# 3-Pumps-Driver.net
KiCad netlist of a schematic drawn in EAGLE
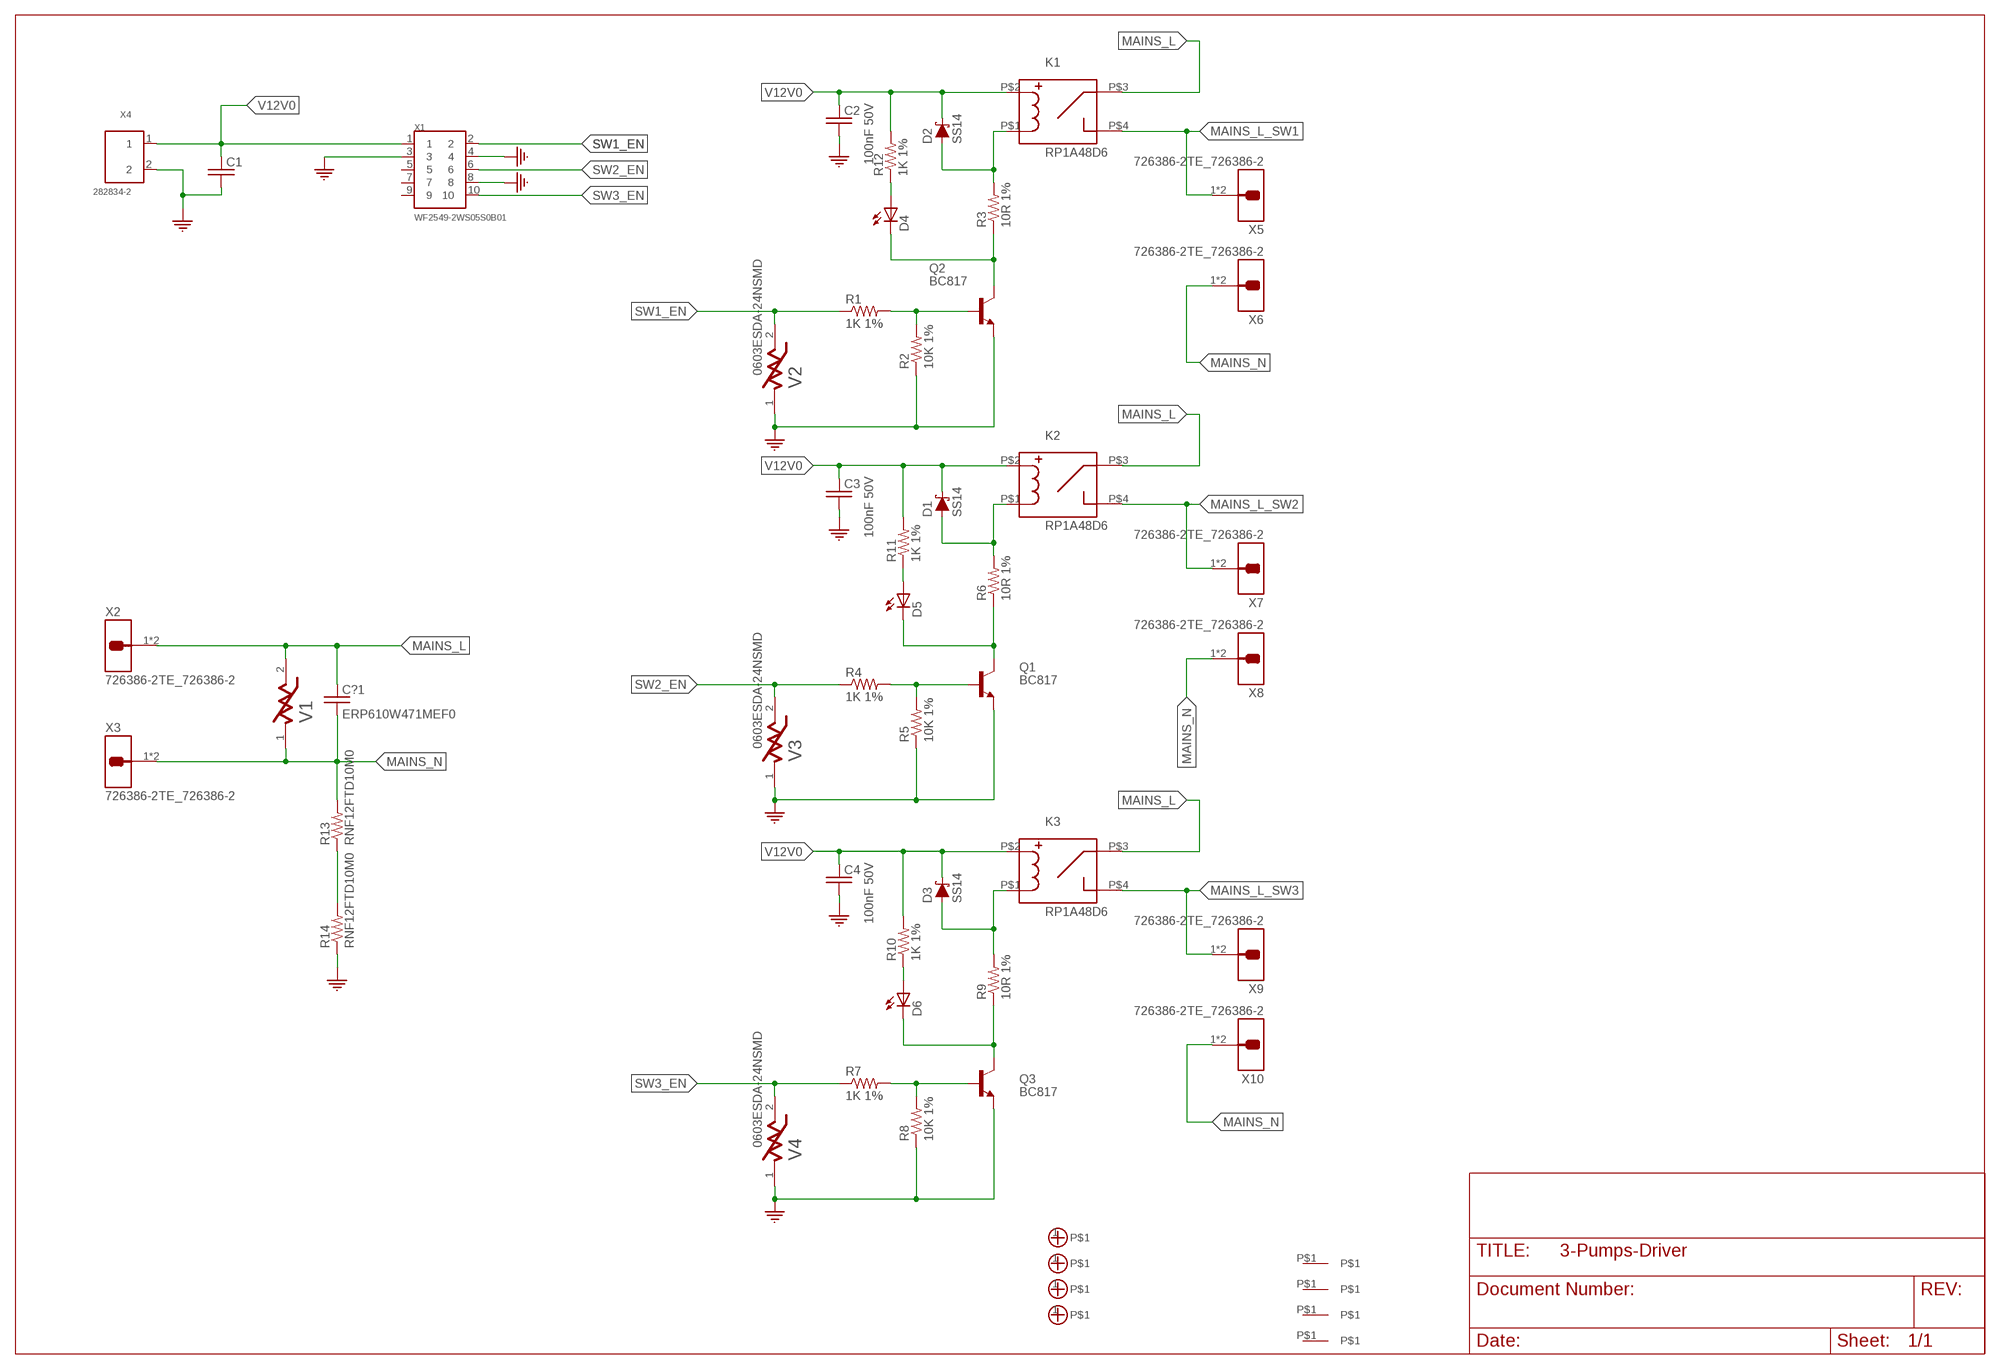
[diagram p0: schematic, sheet 1]

(export (version "E")
  (design (tool "Eeschema 10.0.6"))
  (components
    (comp (ref "C1")
      (value "C_0603EIA0603")
      (footprint "eagle-import:EIA0603")
      (libsource (lib "eagle-import") (part "C_0603EIA0603"))
    )
    (comp (ref "C2")
      (value "100nF 50V")
      (footprint "eagle-import:EIA0603")
      (libsource (lib "eagle-import") (part "C_0603EIA0603"))
    )
    (comp (ref "C3")
      (value "100nF 50V")
      (footprint "eagle-import:EIA0603")
      (libsource (lib "eagle-import") (part "C_0603EIA0603"))
    )
    (comp (ref "C4")
      (value "100nF 50V")
      (footprint "eagle-import:EIA0603")
      (libsource (lib "eagle-import") (part "C_0603EIA0603"))
    )
    (comp (ref "C?1")
      (value "ERP610W471MEF0")
      (footprint "eagle-import:CAPACITOR-FILM-RM12.5MM-12MM")
      (fields (field (name "MFR") "Vishay"))
      (libsource (lib "eagle-import") (part "ERP610W471MEF0"))
    )
    (comp (ref "D1")
      (value "SS14")
      (footprint "eagle-import:SMA")
      (fields (field (name "MFR") "MCC"))
      (libsource (lib "eagle-import") (part "SS14"))
    )
    (comp (ref "D2")
      (value "SS14")
      (footprint "eagle-import:SMA")
      (fields (field (name "MFR") "MCC"))
      (libsource (lib "eagle-import") (part "SS14"))
    )
    (comp (ref "D3")
      (value "SS14")
      (footprint "eagle-import:SMA")
      (fields (field (name "MFR") "MCC"))
      (libsource (lib "eagle-import") (part "SS14"))
    )
    (comp (ref "D4")
      (value "26-21/GPC-F3138B/CA")
      (footprint "eagle-import:SMD1206-LED")
      (fields (field (name "MFR") "Everlight"))
      (libsource (lib "eagle-import") (part "26-21/GPC-F3138B/CA"))
    )
    (comp (ref "D5")
      (value "26-21/GPC-F3138B/CA")
      (footprint "eagle-import:SMD1206-LED")
      (fields (field (name "MFR") "Everlight"))
      (libsource (lib "eagle-import") (part "26-21/GPC-F3138B/CA"))
    )
    (comp (ref "D6")
      (value "26-21/GPC-F3138B/CA")
      (footprint "eagle-import:SMD1206-LED")
      (fields (field (name "MFR") "Everlight"))
      (libsource (lib "eagle-import") (part "26-21/GPC-F3138B/CA"))
    )
    (comp (ref "FID1")
      (value "FIDUCIAL")
      (footprint "eagle-import:FIDUCIAL")
      (libsource (lib "eagle-import") (part "FIDUCIAL"))
    )
    (comp (ref "FID2")
      (value "FIDUCIAL")
      (footprint "eagle-import:FIDUCIAL")
      (libsource (lib "eagle-import") (part "FIDUCIAL"))
    )
    (comp (ref "FID3")
      (value "FIDUCIAL")
      (footprint "eagle-import:FIDUCIAL")
      (libsource (lib "eagle-import") (part "FIDUCIAL"))
    )
    (comp (ref "FID4")
      (value "FIDUCIAL")
      (footprint "eagle-import:FIDUCIAL")
      (libsource (lib "eagle-import") (part "FIDUCIAL"))
    )
    (comp (ref "K1")
      (value "RP1A48D6")
      (footprint "eagle-import:SSR_RP1A")
      (libsource (lib "eagle-import") (part "RP1A48D6"))
    )
    (comp (ref "K2")
      (value "RP1A48D6")
      (footprint "eagle-import:SSR_RP1A")
      (libsource (lib "eagle-import") (part "RP1A48D6"))
    )
    (comp (ref "K3")
      (value "RP1A48D6")
      (footprint "eagle-import:SSR_RP1A")
      (libsource (lib "eagle-import") (part "RP1A48D6"))
    )
    (comp (ref "M1")
      (value "M_HOLE_3M")
      (footprint "eagle-import:PCB_SCREW_M3_POWER")
      (libsource (lib "eagle-import") (part "M_HOLE_3M"))
    )
    (comp (ref "M2")
      (value "M_HOLE_3M")
      (footprint "eagle-import:PCB_SCREW_M3_POWER")
      (libsource (lib "eagle-import") (part "M_HOLE_3M"))
    )
    (comp (ref "M3")
      (value "M_HOLE_3M")
      (footprint "eagle-import:PCB_SCREW_M3_POWER")
      (libsource (lib "eagle-import") (part "M_HOLE_3M"))
    )
    (comp (ref "M4")
      (value "M_HOLE_3M")
      (footprint "eagle-import:PCB_SCREW_M3_POWER")
      (libsource (lib "eagle-import") (part "M_HOLE_3M"))
    )
    (comp (ref "Q1")
      (value "BC817")
      (footprint "eagle-import:SOT23")
      (fields (field (name "MFR") "NXP"))
      (libsource (lib "eagle-import") (part "BC817"))
    )
    (comp (ref "Q2")
      (value "BC817")
      (footprint "eagle-import:SOT23")
      (fields (field (name "MFR") "NXP"))
      (libsource (lib "eagle-import") (part "BC817"))
    )
    (comp (ref "Q3")
      (value "BC817")
      (footprint "eagle-import:SOT23")
      (fields (field (name "MFR") "NXP"))
      (libsource (lib "eagle-import") (part "BC817"))
    )
    (comp (ref "R1")
      (value "1K 1%")
      (footprint "eagle-import:EIA0603")
      (libsource (lib "eagle-import") (part "R_0603"))
    )
    (comp (ref "R2")
      (value "10K 1%")
      (footprint "eagle-import:EIA0603")
      (libsource (lib "eagle-import") (part "R_0603"))
    )
    (comp (ref "R3")
      (value "10R 1%")
      (footprint "eagle-import:EIA1206")
      (libsource (lib "eagle-import") (part "R_1206EIA1206"))
    )
    (comp (ref "R4")
      (value "1K 1%")
      (footprint "eagle-import:EIA0603")
      (libsource (lib "eagle-import") (part "R_0603"))
    )
    (comp (ref "R5")
      (value "10K 1%")
      (footprint "eagle-import:EIA0603")
      (libsource (lib "eagle-import") (part "R_0603"))
    )
    (comp (ref "R6")
      (value "10R 1%")
      (footprint "eagle-import:EIA1206")
      (libsource (lib "eagle-import") (part "R_1206EIA1206"))
    )
    (comp (ref "R7")
      (value "1K 1%")
      (footprint "eagle-import:EIA0603")
      (libsource (lib "eagle-import") (part "R_0603"))
    )
    (comp (ref "R8")
      (value "10K 1%")
      (footprint "eagle-import:EIA0603")
      (libsource (lib "eagle-import") (part "R_0603"))
    )
    (comp (ref "R9")
      (value "10R 1%")
      (footprint "eagle-import:EIA1206")
      (libsource (lib "eagle-import") (part "R_1206EIA1206"))
    )
    (comp (ref "R10")
      (value "1K 1%")
      (footprint "eagle-import:EIA1206")
      (libsource (lib "eagle-import") (part "R_1206EIA1206"))
    )
    (comp (ref "R11")
      (value "1K 1%")
      (footprint "eagle-import:EIA1206")
      (libsource (lib "eagle-import") (part "R_1206EIA1206"))
    )
    (comp (ref "R12")
      (value "1K 1%")
      (footprint "eagle-import:EIA1206")
      (libsource (lib "eagle-import") (part "R_1206EIA1206"))
    )
    (comp (ref "R13")
      (value "RNF12FTD10M0")
      (footprint "eagle-import:RES-RM12.5-VR37")
      (fields (field (name "MFR") "Stackpole Electronics Inc"))
      (libsource (lib "eagle-import") (part "RNF12FTD10M0"))
    )
    (comp (ref "R14")
      (value "RNF12FTD10M0")
      (footprint "eagle-import:RES-RM12.5-VR37")
      (fields (field (name "MFR") "Stackpole Electronics Inc"))
      (libsource (lib "eagle-import") (part "RNF12FTD10M0"))
    )
    (comp (ref "V1")
      (value "B72205S0271K101B72205S2131K101")
      (footprint "eagle-import:EPCOS_B72205S0271K101_0")
      (fields (field (name "MFR") "EPCOS"))
      (libsource (lib "eagle-import") (part "B72205S0271K101B72205S2131K101"))
    )
    (comp (ref "V2")
      (value "0603ESDA-24NSMD")
      (footprint "eagle-import:EIA0603")
      (fields (field (name "MFR") "Bourns"))
      (libsource (lib "eagle-import") (part "0603ESDA-24NSMD"))
    )
    (comp (ref "V3")
      (value "0603ESDA-24NSMD")
      (footprint "eagle-import:EIA0603")
      (fields (field (name "MFR") "Bourns"))
      (libsource (lib "eagle-import") (part "0603ESDA-24NSMD"))
    )
    (comp (ref "V4")
      (value "0603ESDA-24NSMD")
      (footprint "eagle-import:EIA0603")
      (fields (field (name "MFR") "Bourns"))
      (libsource (lib "eagle-import") (part "0603ESDA-24NSMD"))
    )
    (comp (ref "X1")
      (value "WF2549-2WS05S0B01")
      (footprint "eagle-import:X10_100MIL_2XROW_VERT")
      (fields (field (name "MFR") "WCON"))
      (libsource (lib "eagle-import") (part "WF2549-2WS05S0B01"))
    )
    (comp (ref "X2")
      (value "726386-2TE_726386-2")
      (footprint "eagle-import:TE_726386-2")
      (fields
        (field (name "DIGIKEY_PART_NUMBER") "A114371-ND")
        (field (name "MF") "TE")
        (field (name "MOUSER_PART_NUMBER") "571-726386-2")
      )
      (libsource (lib "eagle-import") (part "726386-2TE_726386-2"))
    )
    (comp (ref "X3")
      (value "726386-2TE_726386-2")
      (footprint "eagle-import:TE_726386-2")
      (fields
        (field (name "DIGIKEY_PART_NUMBER") "A114371-ND")
        (field (name "MF") "TE")
        (field (name "MOUSER_PART_NUMBER") "571-726386-2")
      )
      (libsource (lib "eagle-import") (part "726386-2TE_726386-2"))
    )
    (comp (ref "X4")
      (value "282834-2")
      (footprint "eagle-import:TE_282834-2_0")
      (fields (field (name "MFR") "TE"))
      (libsource (lib "eagle-import") (part "282834-2"))
    )
    (comp (ref "X5")
      (value "726386-2TE_726386-2")
      (footprint "eagle-import:TE_726386-2")
      (fields
        (field (name "DIGIKEY_PART_NUMBER") "A114371-ND")
        (field (name "MF") "TE")
        (field (name "MOUSER_PART_NUMBER") "571-726386-2")
      )
      (libsource (lib "eagle-import") (part "726386-2TE_726386-2"))
    )
    (comp (ref "X6")
      (value "726386-2TE_726386-2")
      (footprint "eagle-import:TE_726386-2")
      (fields
        (field (name "DIGIKEY_PART_NUMBER") "A114371-ND")
        (field (name "MF") "TE")
        (field (name "MOUSER_PART_NUMBER") "571-726386-2")
      )
      (libsource (lib "eagle-import") (part "726386-2TE_726386-2"))
    )
    (comp (ref "X7")
      (value "726386-2TE_726386-2")
      (footprint "eagle-import:TE_726386-2")
      (fields
        (field (name "DIGIKEY_PART_NUMBER") "A114371-ND")
        (field (name "MF") "TE")
        (field (name "MOUSER_PART_NUMBER") "571-726386-2")
      )
      (libsource (lib "eagle-import") (part "726386-2TE_726386-2"))
    )
    (comp (ref "X8")
      (value "726386-2TE_726386-2")
      (footprint "eagle-import:TE_726386-2")
      (fields
        (field (name "DIGIKEY_PART_NUMBER") "A114371-ND")
        (field (name "MF") "TE")
        (field (name "MOUSER_PART_NUMBER") "571-726386-2")
      )
      (libsource (lib "eagle-import") (part "726386-2TE_726386-2"))
    )
    (comp (ref "X9")
      (value "726386-2TE_726386-2")
      (footprint "eagle-import:TE_726386-2")
      (fields
        (field (name "DIGIKEY_PART_NUMBER") "A114371-ND")
        (field (name "MF") "TE")
        (field (name "MOUSER_PART_NUMBER") "571-726386-2")
      )
      (libsource (lib "eagle-import") (part "726386-2TE_726386-2"))
    )
    (comp (ref "X10")
      (value "726386-2TE_726386-2")
      (footprint "eagle-import:TE_726386-2")
      (fields
        (field (name "DIGIKEY_PART_NUMBER") "A114371-ND")
        (field (name "MF") "TE")
        (field (name "MOUSER_PART_NUMBER") "571-726386-2")
      )
      (libsource (lib "eagle-import") (part "726386-2TE_726386-2"))
    )
  )
  (nets
    (net (code "1") (name "GND") (class "Default")
      (node (ref "C1") (pin "2") (pinfunction "2_2") (pintype "passive"))
      (node (ref "C2") (pin "2") (pinfunction "2_2") (pintype "passive"))
      (node (ref "C3") (pin "2") (pinfunction "2_2") (pintype "passive"))
      (node (ref "C4") (pin "2") (pinfunction "2_2") (pintype "passive"))
      (node (ref "Q1") (pin "2") (pinfunction "E_2") (pintype "passive"))
      (node (ref "Q2") (pin "2") (pinfunction "E_2") (pintype "passive"))
      (node (ref "Q3") (pin "2") (pinfunction "E_2") (pintype "passive"))
      (node (ref "R14") (pin "1") (pinfunction "1_1") (pintype "passive"))
      (node (ref "R2") (pin "1") (pinfunction "1_1") (pintype "passive"))
      (node (ref "R5") (pin "1") (pinfunction "1_1") (pintype "passive"))
      (node (ref "R8") (pin "1") (pinfunction "1_1") (pintype "passive"))
      (node (ref "V2") (pin "1") (pinfunction "1_1") (pintype "passive"))
      (node (ref "V3") (pin "1") (pinfunction "1_1") (pintype "passive"))
      (node (ref "V4") (pin "1") (pinfunction "1_1") (pintype "passive"))
      (node (ref "X1") (pin "3") (pinfunction "3_3") (pintype "bidirectional"))
      (node (ref "X1") (pin "4") (pinfunction "4_4") (pintype "bidirectional"))
      (node (ref "X1") (pin "8") (pinfunction "8_8") (pintype "bidirectional"))
      (node (ref "X4") (pin "2") (pinfunction "2_2") (pintype "bidirectional"))
    )
    (net (code "2") (name "MAINS_L") (class "Default")
      (node (ref "C?1") (pin "1") (pinfunction "1_1") (pintype "passive"))
      (node (ref "K1") (pin "P$3") (pinfunction "3_P$3") (pintype "passive"))
      (node (ref "K2") (pin "P$3") (pinfunction "3_P$3") (pintype "passive"))
      (node (ref "K3") (pin "P$3") (pinfunction "3_P$3") (pintype "passive"))
      (node (ref "V1") (pin "2") (pinfunction "2_2") (pintype "passive"))
      (node (ref "X2") (pin "1") (pinfunction "1_1") (pintype "passive"))
      (node (ref "X2") (pin "1-2") (pinfunction "1_1-2") (pintype "passive"))
    )
    (net (code "3") (name "MAINS_L_SW1") (class "Default")
      (node (ref "K1") (pin "P$4") (pinfunction "4_P$4") (pintype "passive"))
      (node (ref "X5") (pin "1") (pinfunction "1_1") (pintype "passive"))
      (node (ref "X5") (pin "1-2") (pinfunction "1_1-2") (pintype "passive"))
    )
    (net (code "4") (name "MAINS_L_SW2") (class "Default")
      (node (ref "K2") (pin "P$4") (pinfunction "4_P$4") (pintype "passive"))
      (node (ref "X7") (pin "1") (pinfunction "1_1") (pintype "passive"))
      (node (ref "X7") (pin "1-2") (pinfunction "1_1-2") (pintype "passive"))
    )
    (net (code "5") (name "MAINS_L_SW3") (class "Default")
      (node (ref "K3") (pin "P$4") (pinfunction "4_P$4") (pintype "passive"))
      (node (ref "X9") (pin "1") (pinfunction "1_1") (pintype "passive"))
      (node (ref "X9") (pin "1-2") (pinfunction "1_1-2") (pintype "passive"))
    )
    (net (code "6") (name "MAINS_N") (class "Default")
      (node (ref "C?1") (pin "2") (pinfunction "2_2") (pintype "passive"))
      (node (ref "R13") (pin "2") (pinfunction "2_2") (pintype "passive"))
      (node (ref "V1") (pin "1") (pinfunction "1_1") (pintype "passive"))
      (node (ref "X10") (pin "1") (pinfunction "1_1") (pintype "passive"))
      (node (ref "X10") (pin "1-2") (pinfunction "1_1-2") (pintype "passive"))
      (node (ref "X3") (pin "1") (pinfunction "1_1") (pintype "passive"))
      (node (ref "X3") (pin "1-2") (pinfunction "1_1-2") (pintype "passive"))
      (node (ref "X6") (pin "1") (pinfunction "1_1") (pintype "passive"))
      (node (ref "X6") (pin "1-2") (pinfunction "1_1-2") (pintype "passive"))
      (node (ref "X8") (pin "1") (pinfunction "1_1") (pintype "passive"))
      (node (ref "X8") (pin "1-2") (pinfunction "1_1-2") (pintype "passive"))
    )
    (net (code "7") (name "Net-(D1-A)") (class "Default")
      (node (ref "D1") (pin "2") (pinfunction "A_2") (pintype "passive"))
      (node (ref "K2") (pin "P$1") (pinfunction "1_P$1") (pintype "passive"))
      (node (ref "R6") (pin "2") (pinfunction "2_2") (pintype "passive"))
    )
    (net (code "8") (name "Net-(D2-A)") (class "Default")
      (node (ref "D2") (pin "2") (pinfunction "A_2") (pintype "passive"))
      (node (ref "K1") (pin "P$1") (pinfunction "1_P$1") (pintype "passive"))
      (node (ref "R3") (pin "2") (pinfunction "2_2") (pintype "passive"))
    )
    (net (code "9") (name "Net-(D3-A)") (class "Default")
      (node (ref "D3") (pin "2") (pinfunction "A_2") (pintype "passive"))
      (node (ref "K3") (pin "P$1") (pinfunction "1_P$1") (pintype "passive"))
      (node (ref "R9") (pin "2") (pinfunction "2_2") (pintype "passive"))
    )
    (net (code "10") (name "Net-(D4-A)") (class "Default")
      (node (ref "D4") (pin "1") (pinfunction "A_1") (pintype "passive"))
      (node (ref "R12") (pin "1") (pinfunction "1_1") (pintype "passive"))
    )
    (net (code "11") (name "Net-(D4-C)") (class "Default")
      (node (ref "D4") (pin "2") (pinfunction "C_2") (pintype "passive"))
      (node (ref "Q2") (pin "3") (pinfunction "C_3") (pintype "passive"))
      (node (ref "R3") (pin "1") (pinfunction "1_1") (pintype "passive"))
    )
    (net (code "12") (name "Net-(D5-A)") (class "Default")
      (node (ref "D5") (pin "1") (pinfunction "A_1") (pintype "passive"))
      (node (ref "R11") (pin "1") (pinfunction "1_1") (pintype "passive"))
    )
    (net (code "13") (name "Net-(D5-C)") (class "Default")
      (node (ref "D5") (pin "2") (pinfunction "C_2") (pintype "passive"))
      (node (ref "Q1") (pin "3") (pinfunction "C_3") (pintype "passive"))
      (node (ref "R6") (pin "1") (pinfunction "1_1") (pintype "passive"))
    )
    (net (code "14") (name "Net-(D6-A)") (class "Default")
      (node (ref "D6") (pin "1") (pinfunction "A_1") (pintype "passive"))
      (node (ref "R10") (pin "1") (pinfunction "1_1") (pintype "passive"))
    )
    (net (code "15") (name "Net-(D6-C)") (class "Default")
      (node (ref "D6") (pin "2") (pinfunction "C_2") (pintype "passive"))
      (node (ref "Q3") (pin "3") (pinfunction "C_3") (pintype "passive"))
      (node (ref "R9") (pin "1") (pinfunction "1_1") (pintype "passive"))
    )
    (net (code "16") (name "Net-(Q1-B)") (class "Default")
      (node (ref "Q1") (pin "1") (pinfunction "B_1") (pintype "passive"))
      (node (ref "R4") (pin "2") (pinfunction "2_2") (pintype "passive"))
      (node (ref "R5") (pin "2") (pinfunction "2_2") (pintype "passive"))
    )
    (net (code "17") (name "Net-(Q2-B)") (class "Default")
      (node (ref "Q2") (pin "1") (pinfunction "B_1") (pintype "passive"))
      (node (ref "R1") (pin "2") (pinfunction "2_2") (pintype "passive"))
      (node (ref "R2") (pin "2") (pinfunction "2_2") (pintype "passive"))
    )
    (net (code "18") (name "Net-(Q3-B)") (class "Default")
      (node (ref "Q3") (pin "1") (pinfunction "B_1") (pintype "passive"))
      (node (ref "R7") (pin "2") (pinfunction "2_2") (pintype "passive"))
      (node (ref "R8") (pin "2") (pinfunction "2_2") (pintype "passive"))
    )
    (net (code "19") (name "Net-(R13-Pad1)") (class "Default")
      (node (ref "R13") (pin "1") (pinfunction "1_1") (pintype "passive"))
      (node (ref "R14") (pin "2") (pinfunction "2_2") (pintype "passive"))
    )
    (net (code "20") (name "SW1_EN") (class "Default")
      (node (ref "R1") (pin "1") (pinfunction "1_1") (pintype "passive"))
      (node (ref "V2") (pin "2") (pinfunction "2_2") (pintype "passive"))
      (node (ref "X1") (pin "2") (pinfunction "2_2") (pintype "bidirectional"))
    )
    (net (code "21") (name "SW2_EN") (class "Default")
      (node (ref "R4") (pin "1") (pinfunction "1_1") (pintype "passive"))
      (node (ref "V3") (pin "2") (pinfunction "2_2") (pintype "passive"))
      (node (ref "X1") (pin "6") (pinfunction "6_6") (pintype "bidirectional"))
    )
    (net (code "22") (name "SW3_EN") (class "Default")
      (node (ref "R7") (pin "1") (pinfunction "1_1") (pintype "passive"))
      (node (ref "V4") (pin "2") (pinfunction "2_2") (pintype "passive"))
      (node (ref "X1") (pin "10") (pinfunction "10_10") (pintype "bidirectional"))
    )
    (net (code "23") (name "V12V0") (class "Default")
      (node (ref "C1") (pin "1") (pinfunction "1_1") (pintype "passive"))
      (node (ref "C2") (pin "1") (pinfunction "1_1") (pintype "passive"))
      (node (ref "C3") (pin "1") (pinfunction "1_1") (pintype "passive"))
      (node (ref "C4") (pin "1") (pinfunction "1_1") (pintype "passive"))
      (node (ref "D1") (pin "1") (pinfunction "C_1") (pintype "passive"))
      (node (ref "D2") (pin "1") (pinfunction "C_1") (pintype "passive"))
      (node (ref "D3") (pin "1") (pinfunction "C_1") (pintype "passive"))
      (node (ref "K1") (pin "P$2") (pinfunction "2_P$2") (pintype "passive"))
      (node (ref "K2") (pin "P$2") (pinfunction "2_P$2") (pintype "passive"))
      (node (ref "K3") (pin "P$2") (pinfunction "2_P$2") (pintype "passive"))
      (node (ref "R10") (pin "2") (pinfunction "2_2") (pintype "passive"))
      (node (ref "R11") (pin "2") (pinfunction "2_2") (pintype "passive"))
      (node (ref "R12") (pin "2") (pinfunction "2_2") (pintype "passive"))
      (node (ref "X1") (pin "1") (pinfunction "1_1") (pintype "bidirectional"))
      (node (ref "X4") (pin "1") (pinfunction "1_1") (pintype "bidirectional"))
    )
    (net (code "24") (name "unconnected-(FID1-PadP$1)") (class "Default")
      (node (ref "FID1") (pin "P$1") (pinfunction "P$1_P$1") (pintype "bidirectional"))
    )
    (net (code "25") (name "unconnected-(FID2-PadP$1)") (class "Default")
      (node (ref "FID2") (pin "P$1") (pinfunction "P$1_P$1") (pintype "bidirectional"))
    )
    (net (code "26") (name "unconnected-(FID3-PadP$1)") (class "Default")
      (node (ref "FID3") (pin "P$1") (pinfunction "P$1_P$1") (pintype "bidirectional"))
    )
    (net (code "27") (name "unconnected-(FID4-PadP$1)") (class "Default")
      (node (ref "FID4") (pin "P$1") (pinfunction "P$1_P$1") (pintype "bidirectional"))
    )
    (net (code "28") (name "unconnected-(M1-P$1-Pad1)") (class "Default")
      (node (ref "M1") (pin "1") (pinfunction "P$1_1") (pintype "bidirectional"))
    )
    (net (code "29") (name "unconnected-(M2-P$1-Pad1)") (class "Default")
      (node (ref "M2") (pin "1") (pinfunction "P$1_1") (pintype "bidirectional"))
    )
    (net (code "30") (name "unconnected-(M3-P$1-Pad1)") (class "Default")
      (node (ref "M3") (pin "1") (pinfunction "P$1_1") (pintype "bidirectional"))
    )
    (net (code "31") (name "unconnected-(M4-P$1-Pad1)") (class "Default")
      (node (ref "M4") (pin "1") (pinfunction "P$1_1") (pintype "bidirectional"))
    )
    (net (code "32") (name "unconnected-(X1-Pad5)") (class "Default")
      (node (ref "X1") (pin "5") (pinfunction "5_5") (pintype "bidirectional"))
    )
    (net (code "33") (name "unconnected-(X1-Pad7)") (class "Default")
      (node (ref "X1") (pin "7") (pinfunction "7_7") (pintype "bidirectional"))
    )
    (net (code "34") (name "unconnected-(X1-Pad9)") (class "Default")
      (node (ref "X1") (pin "9") (pinfunction "9_9") (pintype "bidirectional"))
    )
  )
)
